# SCH_relay-based-x-mas-lights_2021-08-14.net
KiCad netlist of a schematic drawn in EasyEDA
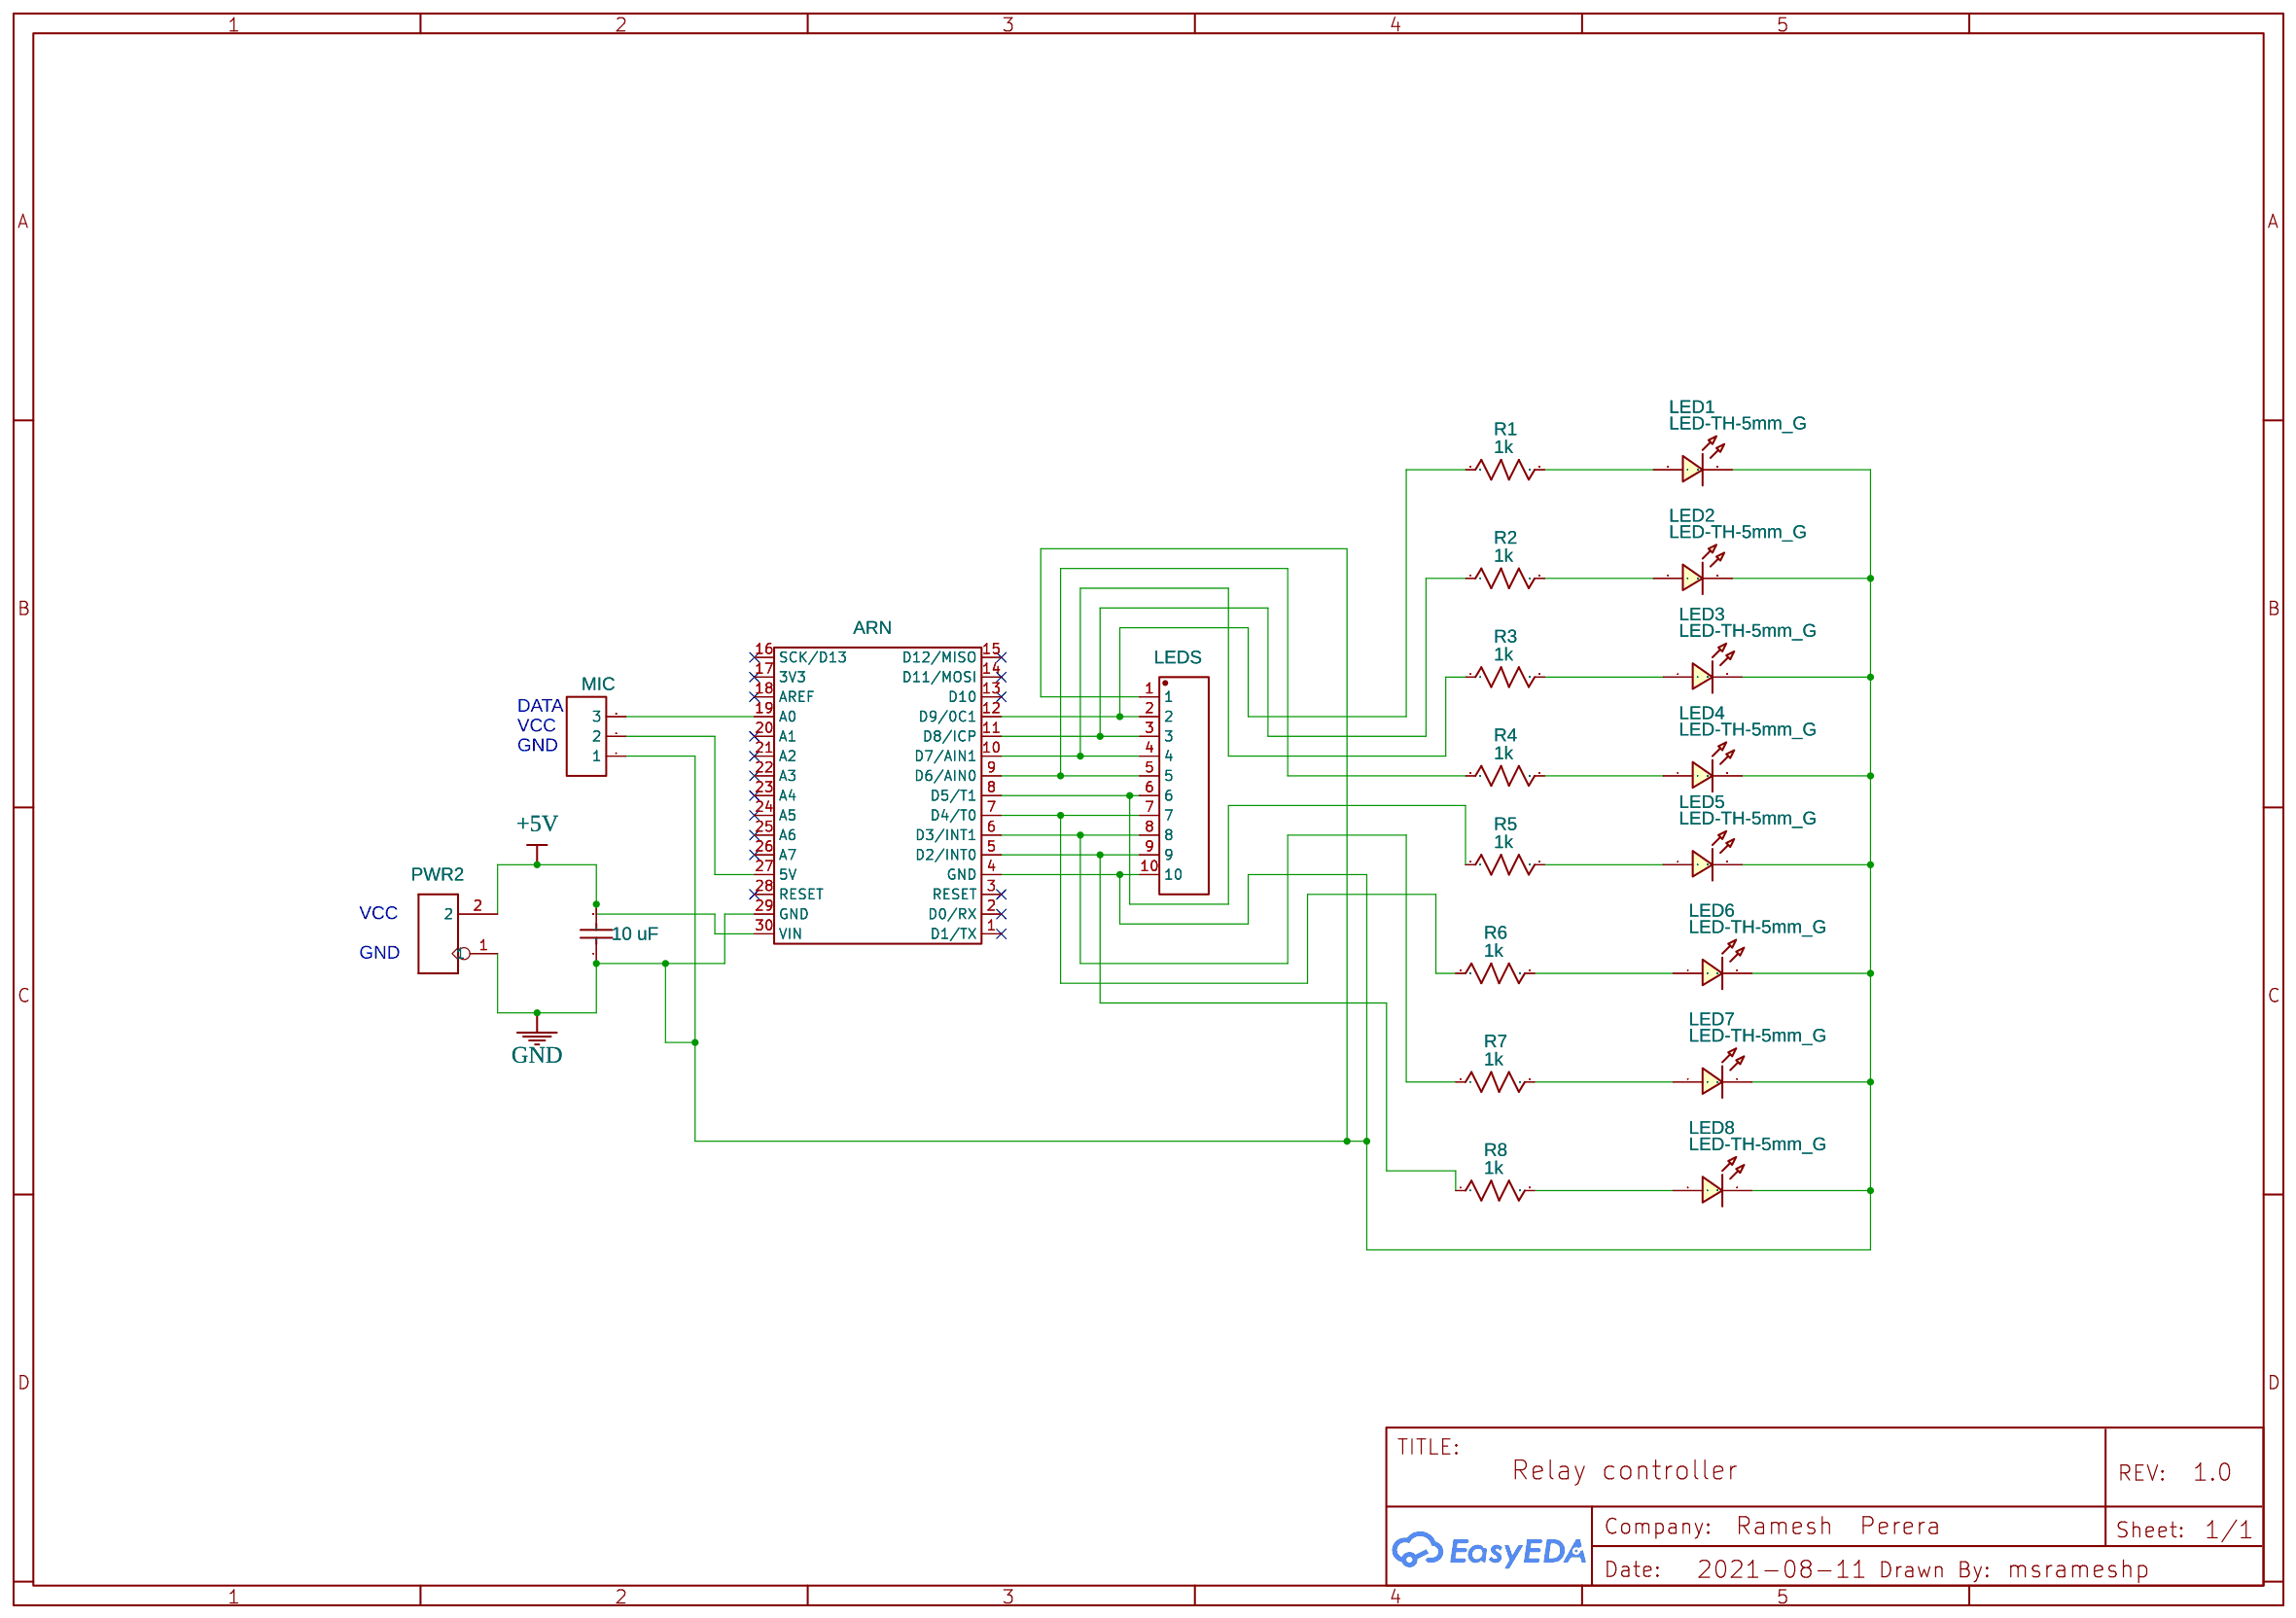
[diagram p0: schematic sheet]

(export (version "E")
  (design (tool "Eeschema 10.0.6"))
  (components
    (comp (ref "ARN") (value "Arduino_Nano_Header") (libsource (lib "") (part "Arduino_Nano_Header")))
    (comp (ref "C2")
      (value "10 uF")
      (fields
        (field (name "BOM_Manufacturer Part") "Ceramic capacitors47PF 3KV")
        (field (name "BOM_Supplier Part") "C19375")
      )
      (libsource (lib "") (part "Ceramic capacitors47PF 3KV"))
    )
    (comp (ref "LED1")
      (value "LED-TH-5mm_G")
      (fields
        (field (name "BOM_Manufacturer Part") "333-2SYGD/S530-E2")
        (field (name "BOM_Supplier Part") "C88163")
      )
      (libsource (lib "") (part "LED-TH-5mm_G"))
    )
    (comp (ref "LED2")
      (value "LED-TH-5mm_G")
      (fields
        (field (name "BOM_Manufacturer Part") "333-2SYGD/S530-E2")
        (field (name "BOM_Supplier Part") "C88163")
      )
      (libsource (lib "") (part "LED-TH-5mm_G"))
    )
    (comp (ref "LED3")
      (value "LED-TH-5mm_G")
      (fields
        (field (name "BOM_Manufacturer Part") "333-2SYGD/S530-E2")
        (field (name "BOM_Supplier Part") "C88163")
      )
      (libsource (lib "") (part "LED-TH-5mm_G"))
    )
    (comp (ref "LED4")
      (value "LED-TH-5mm_G")
      (fields
        (field (name "BOM_Manufacturer Part") "333-2SYGD/S530-E2")
        (field (name "BOM_Supplier Part") "C88163")
      )
      (libsource (lib "") (part "LED-TH-5mm_G"))
    )
    (comp (ref "LED5")
      (value "LED-TH-5mm_G")
      (fields
        (field (name "BOM_Manufacturer Part") "333-2SYGD/S530-E2")
        (field (name "BOM_Supplier Part") "C88163")
      )
      (libsource (lib "") (part "LED-TH-5mm_G"))
    )
    (comp (ref "LED6")
      (value "LED-TH-5mm_G")
      (fields
        (field (name "BOM_Manufacturer Part") "333-2SYGD/S530-E2")
        (field (name "BOM_Supplier Part") "C88163")
      )
      (libsource (lib "") (part "LED-TH-5mm_G"))
    )
    (comp (ref "LED7")
      (value "LED-TH-5mm_G")
      (fields
        (field (name "BOM_Manufacturer Part") "333-2SYGD/S530-E2")
        (field (name "BOM_Supplier Part") "C88163")
      )
      (libsource (lib "") (part "LED-TH-5mm_G"))
    )
    (comp (ref "LED8")
      (value "LED-TH-5mm_G")
      (fields
        (field (name "BOM_Manufacturer Part") "333-2SYGD/S530-E2")
        (field (name "BOM_Supplier Part") "C88163")
      )
      (libsource (lib "") (part "LED-TH-5mm_G"))
    )
    (comp (ref "LEDS")
      (value "Header-Male-2.54_1x10")
      (fields
        (field (name "BOM_Manufacturer Part") "Headers  Pins2.54mm1*10P")
        (field (name "BOM_Supplier Part") "C57369")
      )
      (libsource (lib "") (part "Header-Male-2.54_1x10"))
    )
    (comp (ref "MIC1")
      (value "MIC")
      (fields
        (field (name "BOM_Manufacturer Part") "Header2.54mm 1*3P")
        (field (name "BOM_Supplier Part") "C49257")
      )
      (libsource (lib "") (part "Header-Male-2.54_1x3"))
    )
    (comp (ref "PWR2")
      (value "PWR")
      (fields (field (name "BOM_Manufacturer Part") "P125-1102A0BS116A2"))
      (libsource (lib "") (part "P125-1102A0BS116A2"))
    )
    (comp (ref "R1") (value "1k") (libsource (lib "") (part "R_AXIAL-0.3_US")))
    (comp (ref "R2") (value "1k") (libsource (lib "") (part "R_AXIAL-0.3_US")))
    (comp (ref "R3") (value "1k") (libsource (lib "") (part "R_AXIAL-0.3_US")))
    (comp (ref "R4") (value "1k") (libsource (lib "") (part "R_AXIAL-0.3_US")))
    (comp (ref "R5") (value "1k") (libsource (lib "") (part "R_AXIAL-0.3_US")))
    (comp (ref "R6") (value "1k") (libsource (lib "") (part "R_AXIAL-0.3_US")))
    (comp (ref "R7") (value "1k") (libsource (lib "") (part "R_AXIAL-0.3_US")))
    (comp (ref "R8") (value "1k") (libsource (lib "") (part "R_AXIAL-0.3_US")))
  )
  (nets
    (net (code "1") (name "+5V") (class "Default")
      (node (ref "ARN") (pin "30") (pinfunction "VIN_30") (pintype "unspecified"))
      (node (ref "C2") (pin "2") (pinfunction "2_2") (pintype "input"))
      (node (ref "PWR2") (pin "2") (pinfunction "2_2") (pintype "unspecified"))
    )
    (net (code "2") (name "GND") (class "Default")
      (node (ref "ARN") (pin "29") (pinfunction "GND_29") (pintype "unspecified"))
      (node (ref "ARN") (pin "4") (pinfunction "GND_4") (pintype "unspecified"))
      (node (ref "C2") (pin "1") (pinfunction "1_1") (pintype "input"))
      (node (ref "LED1") (pin "2") (pinfunction "2_2") (pintype "unspecified"))
      (node (ref "LED2") (pin "2") (pinfunction "2_2") (pintype "unspecified"))
      (node (ref "LED3") (pin "2") (pinfunction "2_2") (pintype "unspecified"))
      (node (ref "LED4") (pin "2") (pinfunction "2_2") (pintype "unspecified"))
      (node (ref "LED5") (pin "2") (pinfunction "2_2") (pintype "unspecified"))
      (node (ref "LED6") (pin "2") (pinfunction "2_2") (pintype "unspecified"))
      (node (ref "LED7") (pin "2") (pinfunction "2_2") (pintype "unspecified"))
      (node (ref "LED8") (pin "2") (pinfunction "2_2") (pintype "unspecified"))
      (node (ref "LEDS") (pin "1") (pinfunction "1_1") (pintype "unspecified"))
      (node (ref "LEDS") (pin "10") (pinfunction "10_10") (pintype "unspecified"))
      (node (ref "MIC1") (pin "1") (pinfunction "1_1") (pintype "input"))
      (node (ref "PWR2") (pin "1") (pinfunction "1_1") (pintype "unspecified"))
    )
    (net (code "3") (name "Net-(ARN-5V)") (class "Default")
      (node (ref "ARN") (pin "27") (pinfunction "5V_27") (pintype "unspecified"))
      (node (ref "MIC1") (pin "2") (pinfunction "2_2") (pintype "input"))
    )
    (net (code "4") (name "Net-(ARN-A0)") (class "Default")
      (node (ref "ARN") (pin "19") (pinfunction "A0_19") (pintype "unspecified"))
      (node (ref "MIC1") (pin "3") (pinfunction "3_3") (pintype "input"))
    )
    (net (code "5") (name "Net-(ARN-D2{slash}INT0)") (class "Default")
      (node (ref "ARN") (pin "5") (pinfunction "D2/INT0_5") (pintype "unspecified"))
      (node (ref "LEDS") (pin "9") (pinfunction "9_9") (pintype "unspecified"))
      (node (ref "R8") (pin "1") (pinfunction "1_1") (pintype "unspecified"))
    )
    (net (code "6") (name "Net-(ARN-D3{slash}INT1)") (class "Default")
      (node (ref "ARN") (pin "6") (pinfunction "D3/INT1_6") (pintype "unspecified"))
      (node (ref "LEDS") (pin "8") (pinfunction "8_8") (pintype "unspecified"))
      (node (ref "R7") (pin "1") (pinfunction "1_1") (pintype "unspecified"))
    )
    (net (code "7") (name "Net-(ARN-D4{slash}T0)") (class "Default")
      (node (ref "ARN") (pin "7") (pinfunction "D4/T0_7") (pintype "unspecified"))
      (node (ref "LEDS") (pin "7") (pinfunction "7_7") (pintype "unspecified"))
      (node (ref "R6") (pin "1") (pinfunction "1_1") (pintype "unspecified"))
    )
    (net (code "8") (name "Net-(ARN-D5{slash}T1)") (class "Default")
      (node (ref "ARN") (pin "8") (pinfunction "D5/T1_8") (pintype "unspecified"))
      (node (ref "LEDS") (pin "6") (pinfunction "6_6") (pintype "unspecified"))
      (node (ref "R5") (pin "1") (pinfunction "1_1") (pintype "unspecified"))
    )
    (net (code "9") (name "Net-(ARN-D6{slash}AIN0)") (class "Default")
      (node (ref "ARN") (pin "9") (pinfunction "D6/AIN0_9") (pintype "unspecified"))
      (node (ref "LEDS") (pin "5") (pinfunction "5_5") (pintype "unspecified"))
      (node (ref "R4") (pin "1") (pinfunction "1_1") (pintype "unspecified"))
    )
    (net (code "10") (name "Net-(ARN-D7{slash}AIN1)") (class "Default")
      (node (ref "ARN") (pin "10") (pinfunction "D7/AIN1_10") (pintype "unspecified"))
      (node (ref "LEDS") (pin "4") (pinfunction "4_4") (pintype "unspecified"))
      (node (ref "R3") (pin "1") (pinfunction "1_1") (pintype "unspecified"))
    )
    (net (code "11") (name "Net-(ARN-D8{slash}ICP)") (class "Default")
      (node (ref "ARN") (pin "11") (pinfunction "D8/ICP_11") (pintype "unspecified"))
      (node (ref "LEDS") (pin "3") (pinfunction "3_3") (pintype "unspecified"))
      (node (ref "R2") (pin "1") (pinfunction "1_1") (pintype "unspecified"))
    )
    (net (code "12") (name "Net-(ARN-D9{slash}0C1)") (class "Default")
      (node (ref "ARN") (pin "12") (pinfunction "D9/0C1_12") (pintype "unspecified"))
      (node (ref "LEDS") (pin "2") (pinfunction "2_2") (pintype "unspecified"))
      (node (ref "R1") (pin "1") (pinfunction "1_1") (pintype "unspecified"))
    )
    (net (code "13") (name "Net-(LED1-Pad1)") (class "Default")
      (node (ref "LED1") (pin "1") (pinfunction "1_1") (pintype "unspecified"))
      (node (ref "R1") (pin "2") (pinfunction "2_2") (pintype "unspecified"))
    )
    (net (code "14") (name "Net-(LED2-Pad1)") (class "Default")
      (node (ref "LED2") (pin "1") (pinfunction "1_1") (pintype "unspecified"))
      (node (ref "R2") (pin "2") (pinfunction "2_2") (pintype "unspecified"))
    )
    (net (code "15") (name "Net-(LED3-Pad1)") (class "Default")
      (node (ref "LED3") (pin "1") (pinfunction "1_1") (pintype "unspecified"))
      (node (ref "R3") (pin "2") (pinfunction "2_2") (pintype "unspecified"))
    )
    (net (code "16") (name "Net-(LED4-Pad1)") (class "Default")
      (node (ref "LED4") (pin "1") (pinfunction "1_1") (pintype "unspecified"))
      (node (ref "R4") (pin "2") (pinfunction "2_2") (pintype "unspecified"))
    )
    (net (code "17") (name "Net-(LED5-Pad1)") (class "Default")
      (node (ref "LED5") (pin "1") (pinfunction "1_1") (pintype "unspecified"))
      (node (ref "R5") (pin "2") (pinfunction "2_2") (pintype "unspecified"))
    )
    (net (code "18") (name "Net-(LED6-Pad1)") (class "Default")
      (node (ref "LED6") (pin "1") (pinfunction "1_1") (pintype "unspecified"))
      (node (ref "R6") (pin "2") (pinfunction "2_2") (pintype "unspecified"))
    )
    (net (code "19") (name "Net-(LED7-Pad1)") (class "Default")
      (node (ref "LED7") (pin "1") (pinfunction "1_1") (pintype "unspecified"))
      (node (ref "R7") (pin "2") (pinfunction "2_2") (pintype "unspecified"))
    )
    (net (code "20") (name "Net-(LED8-Pad1)") (class "Default")
      (node (ref "LED8") (pin "1") (pinfunction "1_1") (pintype "unspecified"))
      (node (ref "R8") (pin "2") (pinfunction "2_2") (pintype "unspecified"))
    )
    (net (code "21") (name "unconnected-(ARN-3V3-Pad17)") (class "Default")
      (node (ref "ARN") (pin "17") (pinfunction "3V3_17") (pintype "unspecified+no_connect"))
    )
    (net (code "22") (name "unconnected-(ARN-A1-Pad20)") (class "Default")
      (node (ref "ARN") (pin "20") (pinfunction "A1_20") (pintype "unspecified+no_connect"))
    )
    (net (code "23") (name "unconnected-(ARN-A2-Pad21)") (class "Default")
      (node (ref "ARN") (pin "21") (pinfunction "A2_21") (pintype "unspecified+no_connect"))
    )
    (net (code "24") (name "unconnected-(ARN-A3-Pad22)") (class "Default")
      (node (ref "ARN") (pin "22") (pinfunction "A3_22") (pintype "unspecified+no_connect"))
    )
    (net (code "25") (name "unconnected-(ARN-A4-Pad23)") (class "Default")
      (node (ref "ARN") (pin "23") (pinfunction "A4_23") (pintype "unspecified+no_connect"))
    )
    (net (code "26") (name "unconnected-(ARN-A5-Pad24)") (class "Default")
      (node (ref "ARN") (pin "24") (pinfunction "A5_24") (pintype "unspecified+no_connect"))
    )
    (net (code "27") (name "unconnected-(ARN-A6-Pad25)") (class "Default")
      (node (ref "ARN") (pin "25") (pinfunction "A6_25") (pintype "unspecified+no_connect"))
    )
    (net (code "28") (name "unconnected-(ARN-A7-Pad26)") (class "Default")
      (node (ref "ARN") (pin "26") (pinfunction "A7_26") (pintype "unspecified+no_connect"))
    )
    (net (code "29") (name "unconnected-(ARN-AREF-Pad18)") (class "Default")
      (node (ref "ARN") (pin "18") (pinfunction "AREF_18") (pintype "unspecified+no_connect"))
    )
    (net (code "30") (name "unconnected-(ARN-D0{slash}RX-Pad2)") (class "Default")
      (node (ref "ARN") (pin "2") (pinfunction "D0/RX_2") (pintype "unspecified+no_connect"))
    )
    (net (code "31") (name "unconnected-(ARN-D1{slash}TX-Pad1)") (class "Default")
      (node (ref "ARN") (pin "1") (pinfunction "D1/TX_1") (pintype "unspecified+no_connect"))
    )
    (net (code "32") (name "unconnected-(ARN-D10-Pad13)") (class "Default")
      (node (ref "ARN") (pin "13") (pinfunction "D10_13") (pintype "unspecified+no_connect"))
    )
    (net (code "33") (name "unconnected-(ARN-D11{slash}MOSI-Pad14)") (class "Default")
      (node (ref "ARN") (pin "14") (pinfunction "D11/MOSI_14") (pintype "unspecified+no_connect"))
    )
    (net (code "34") (name "unconnected-(ARN-D12{slash}MISO-Pad15)") (class "Default")
      (node (ref "ARN") (pin "15") (pinfunction "D12/MISO_15") (pintype "unspecified+no_connect"))
    )
    (net (code "35") (name "unconnected-(ARN-RESET-Pad3)") (class "Default")
      (node (ref "ARN") (pin "3") (pinfunction "RESET_3") (pintype "unspecified+no_connect"))
    )
    (net (code "36") (name "unconnected-(ARN-RESET-Pad28)") (class "Default")
      (node (ref "ARN") (pin "28") (pinfunction "RESET_28") (pintype "unspecified+no_connect"))
    )
    (net (code "37") (name "unconnected-(ARN-SCK{slash}D13-Pad16)") (class "Default")
      (node (ref "ARN") (pin "16") (pinfunction "SCK/D13_16") (pintype "unspecified+no_connect"))
    )
  )
)
